# MorseKOB-Loop-w_PS_v6_eagle.net
KiCad netlist of a schematic drawn in EAGLE
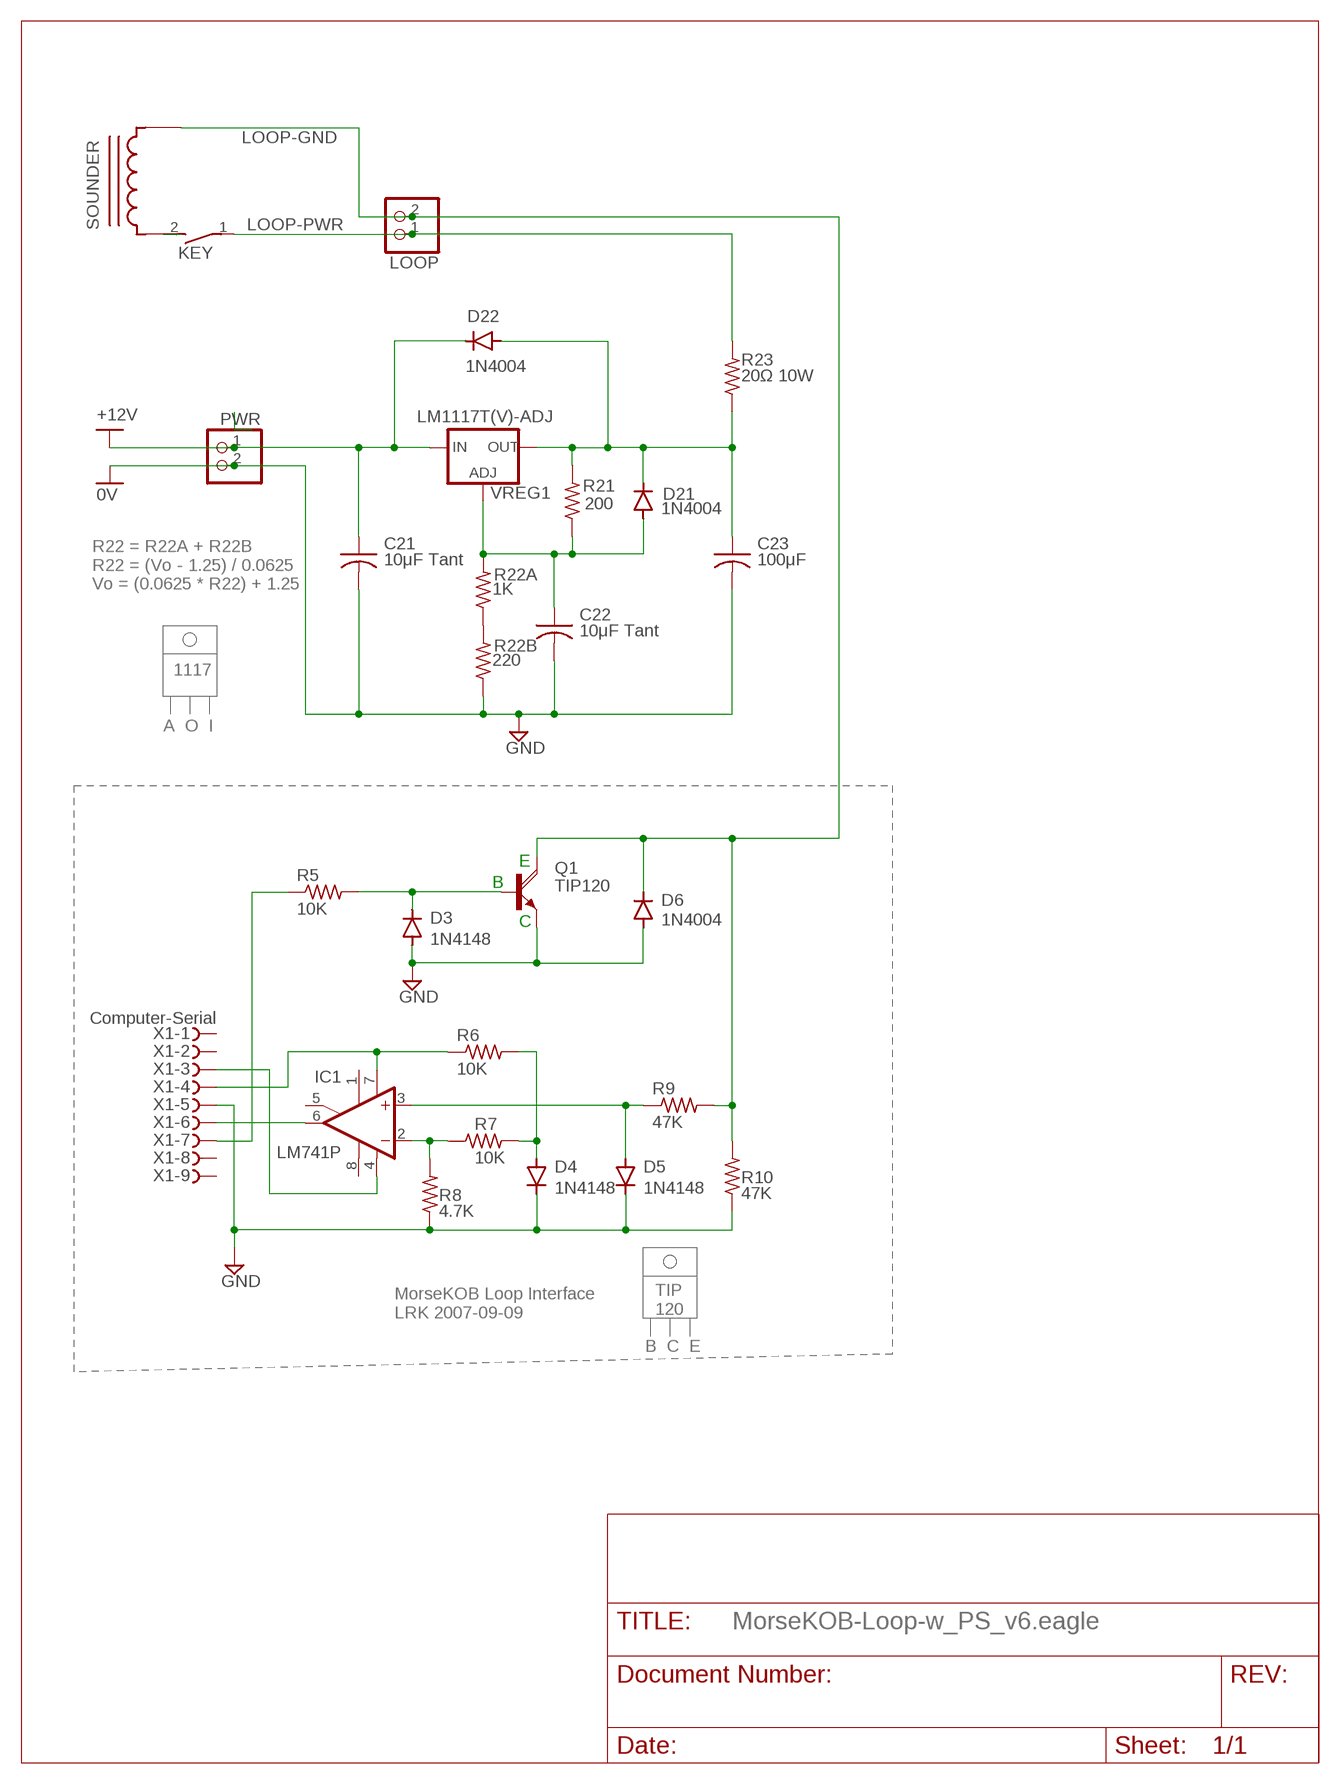
[diagram p0: schematic, sheet 1]

(export (version "E")
  (design (tool "Eeschema 10.0.6"))
  (components
    (comp (ref "C21")
      (value "10μF Tant")
      (footprint "eagle-import:C050-075X075")
      (libsource (lib "eagle-import") (part "C-US050-075X075"))
    )
    (comp (ref "C22")
      (value "10μF Tant")
      (footprint "eagle-import:C050-075X075")
      (libsource (lib "eagle-import") (part "C-US050-075X075"))
    )
    (comp (ref "C23")
      (value "100μF")
      (footprint "eagle-import:C025-050X050")
      (libsource (lib "eagle-import") (part "C-US025-050X050"))
    )
    (comp (ref "D3")
      (value "1N4148DO35-7")
      (footprint "eagle-import:DO35-7")
      (fields (field (name "TYPE") "1N4148"))
      (libsource (lib "eagle-import") (part "1N4148DO35-7"))
    )
    (comp (ref "D4")
      (value "1N4148DO35-7")
      (footprint "eagle-import:DO35-7")
      (fields (field (name "TYPE") "1N4148"))
      (libsource (lib "eagle-import") (part "1N4148DO35-7"))
    )
    (comp (ref "D5")
      (value "1N4148DO35-7")
      (footprint "eagle-import:DO35-7")
      (fields (field (name "TYPE") "1N4148"))
      (libsource (lib "eagle-import") (part "1N4148DO35-7"))
    )
    (comp (ref "D6")
      (value "1N4004")
      (footprint "eagle-import:DO41-10")
      (libsource (lib "eagle-import") (part "diode_210_1N4004"))
    )
    (comp (ref "D21")
      (value "1N4004")
      (footprint "eagle-import:DO-41")
      (fields
        (field (name "DIGIKEY_PART_NUMBER") "1N4004MSCT-ND")
        (field (name "MANUFACTURER") "Micro Commercial Co")
        (field (name "CREATED_BY") "PCBLayout.com")
      )
      (libsource (lib "eagle-import") (part "1N4004"))
    )
    (comp (ref "D22")
      (value "1N4004")
      (footprint "eagle-import:DO-41")
      (fields
        (field (name "DIGIKEY_PART_NUMBER") "1N4004MSCT-ND")
        (field (name "MANUFACTURER") "Micro Commercial Co")
        (field (name "CREATED_BY") "PCBLayout.com")
      )
      (libsource (lib "eagle-import") (part "1N4004"))
    )
    (comp (ref "IC1")
      (value "LM741P")
      (footprint "eagle-import:DIL08")
      (libsource (lib "eagle-import") (part "741PLM"))
    )
    (comp (ref "KEY")
      (value "DS01E")
      (footprint "eagle-import:DS-01")
      (libsource (lib "eagle-import") (part "DS01E"))
    )
    (comp (ref "LOOP")
      (value "PINHD-1X2")
      (footprint "eagle-import:1X02")
      (libsource (lib "eagle-import") (part "PINHD-1X2"))
    )
    (comp (ref "PWR")
      (value "PINHD-1X2")
      (footprint "eagle-import:1X02")
      (libsource (lib "eagle-import") (part "PINHD-1X2"))
    )
    (comp (ref "Q1")
      (value "TIP120")
      (footprint "eagle-import:TO220AH")
      (libsource (lib "eagle-import") (part "TIP120"))
    )
    (comp (ref "R5")
      (value "10K")
      (footprint "eagle-import:0207_10")
      (libsource (lib "eagle-import") (part "R-US_0207/10"))
    )
    (comp (ref "R6")
      (value "10K")
      (footprint "eagle-import:0207_10")
      (libsource (lib "eagle-import") (part "R-US_0207/10"))
    )
    (comp (ref "R7")
      (value "10K")
      (footprint "eagle-import:0207_10")
      (libsource (lib "eagle-import") (part "R-US_0207/10"))
    )
    (comp (ref "R8")
      (value "4.7K")
      (footprint "eagle-import:0207_10")
      (libsource (lib "eagle-import") (part "R-US_0207/10"))
    )
    (comp (ref "R9")
      (value "47K")
      (footprint "eagle-import:0207_10")
      (libsource (lib "eagle-import") (part "R-US_0207/10"))
    )
    (comp (ref "R10")
      (value "47K")
      (footprint "eagle-import:0207_10")
      (libsource (lib "eagle-import") (part "R-US_0207/10"))
    )
    (comp (ref "R21")
      (value "200")
      (footprint "eagle-import:0207_10")
      (libsource (lib "eagle-import") (part "R-US_0207/10"))
    )
    (comp (ref "R22A")
      (value "1K")
      (footprint "eagle-import:0207_10")
      (libsource (lib "eagle-import") (part "R-US_0207/10"))
    )
    (comp (ref "R22B")
      (value "220")
      (footprint "eagle-import:0207_10")
      (libsource (lib "eagle-import") (part "R-US_0207/10"))
    )
    (comp (ref "R23")
      (value "20Ω 10W")
      (footprint "eagle-import:0922_22")
      (libsource (lib "eagle-import") (part "R-US_0922/22"))
    )
    (comp (ref "SOUNDER")
      (value "T37_INDUCTOR")
      (footprint "eagle-import:T37_INDUCTOR")
      (libsource (lib "eagle-import") (part "T37_INDUCTOR"))
    )
    (comp (ref "VREG1")
      (value "LM1117T(V)-ADJ")
      (footprint "eagle-import:TO220V")
      (fields (field (name "MF") "Texas Instruments") (field (name "MPN") "LM1777T-ADJ"))
      (libsource (lib "eagle-import") (part "LM1117?-ADJT(V)"))
    )
    (comp (ref "X1")
      (value "Computer-Serial")
      (footprint "eagle-import:177-009-FEMALE")
      (libsource (lib "eagle-import") (part "F09?S.590"))
    )
  )
  (nets
    (net (code "1") (name "+12V") (class "Default")
      (node (ref "C21") (pin "1") (pinfunction "1_1") (pintype "passive"))
      (node (ref "D22") (pin "C") (pinfunction "C_C") (pintype "passive"))
      (node (ref "PWR") (pin "1") (pinfunction "1_1") (pintype "passive"))
      (node (ref "VREG1") (pin "3") (pinfunction "IN_3") (pintype "input"))
    )
    (net (code "2") (name "/LOOP-GND") (class "Default")
      (node (ref "D6") (pin "C") (pinfunction "C_C") (pintype "passive"))
      (node (ref "LOOP") (pin "2") (pinfunction "2_2") (pintype "passive"))
      (node (ref "Q1") (pin "C") (pinfunction "C_C") (pintype "passive"))
      (node (ref "R10") (pin "2") (pinfunction "2_2") (pintype "passive"))
      (node (ref "R9") (pin "2") (pinfunction "2_2") (pintype "passive"))
      (node (ref "SOUNDER") (pin "CA") (pinfunction "CA_CA") (pintype "bidirectional"))
    )
    (net (code "3") (name "/LOOP-PWR") (class "Default")
      (node (ref "KEY") (pin "1") (pinfunction "1_1") (pintype "passive"))
      (node (ref "LOOP") (pin "1") (pinfunction "1_1") (pintype "passive"))
      (node (ref "R23") (pin "2") (pinfunction "2_2") (pintype "passive"))
    )
    (net (code "4") (name "0V") (class "Default")
      (node (ref "C21") (pin "2") (pinfunction "2_2") (pintype "passive"))
      (node (ref "C22") (pin "2") (pinfunction "2_2") (pintype "passive"))
      (node (ref "C23") (pin "2") (pinfunction "2_2") (pintype "passive"))
      (node (ref "D3") (pin "A") (pinfunction "A_A") (pintype "passive"))
      (node (ref "D4") (pin "C") (pinfunction "C_C") (pintype "passive"))
      (node (ref "D5") (pin "C") (pinfunction "C_C") (pintype "passive"))
      (node (ref "D6") (pin "A") (pinfunction "A_A") (pintype "passive"))
      (node (ref "PWR") (pin "2") (pinfunction "2_2") (pintype "passive"))
      (node (ref "Q1") (pin "E") (pinfunction "E_E") (pintype "passive"))
      (node (ref "R10") (pin "1") (pinfunction "1_1") (pintype "passive"))
      (node (ref "R22B") (pin "1") (pinfunction "1_1") (pintype "passive"))
      (node (ref "R8") (pin "1") (pinfunction "1_1") (pintype "passive"))
      (node (ref "X1") (pin "5") (pinfunction "F_5") (pintype "passive"))
    )
    (net (code "5") (name "Net-(D3-PadC)") (class "Default")
      (node (ref "D3") (pin "C") (pinfunction "C_C") (pintype "passive"))
      (node (ref "Q1") (pin "B") (pinfunction "B_B") (pintype "passive"))
      (node (ref "R5") (pin "2") (pinfunction "2_2") (pintype "passive"))
    )
    (net (code "6") (name "Net-(D4-PadA)") (class "Default")
      (node (ref "D4") (pin "A") (pinfunction "A_A") (pintype "passive"))
      (node (ref "R6") (pin "2") (pinfunction "2_2") (pintype "passive"))
      (node (ref "R7") (pin "2") (pinfunction "2_2") (pintype "passive"))
    )
    (net (code "7") (name "Net-(IC1-+IN)") (class "Default")
      (node (ref "D5") (pin "A") (pinfunction "A_A") (pintype "passive"))
      (node (ref "IC1") (pin "3") (pinfunction "+IN_3") (pintype "input"))
      (node (ref "R9") (pin "1") (pinfunction "1_1") (pintype "passive"))
    )
    (net (code "8") (name "Net-(IC1--IN)") (class "Default")
      (node (ref "IC1") (pin "2") (pinfunction "-IN_2") (pintype "input"))
      (node (ref "R7") (pin "1") (pinfunction "1_1") (pintype "passive"))
      (node (ref "R8") (pin "2") (pinfunction "2_2") (pintype "passive"))
    )
    (net (code "9") (name "Net-(IC1-OUT)") (class "Default")
      (node (ref "IC1") (pin "6") (pinfunction "OUT_6") (pintype "output"))
      (node (ref "X1") (pin "6") (pinfunction "F_6") (pintype "passive"))
    )
    (net (code "10") (name "Net-(IC1-V+)") (class "Default")
      (node (ref "IC1") (pin "7") (pinfunction "V+_7") (pintype "power_in"))
      (node (ref "R6") (pin "1") (pinfunction "1_1") (pintype "passive"))
      (node (ref "X1") (pin "4") (pinfunction "F_4") (pintype "passive"))
    )
    (net (code "11") (name "Net-(IC1-V-)") (class "Default")
      (node (ref "IC1") (pin "4") (pinfunction "V-_4") (pintype "power_in"))
      (node (ref "X1") (pin "3") (pinfunction "F_3") (pintype "passive"))
    )
    (net (code "12") (name "Net-(KEY-Pad2)") (class "Default")
      (node (ref "KEY") (pin "2") (pinfunction "2_2") (pintype "passive"))
      (node (ref "SOUNDER") (pin "CB") (pinfunction "CB_CB") (pintype "bidirectional"))
    )
    (net (code "13") (name "Net-(R22A-Pad1)") (class "Default")
      (node (ref "R22A") (pin "1") (pinfunction "1_1") (pintype "passive"))
      (node (ref "R22B") (pin "2") (pinfunction "2_2") (pintype "passive"))
    )
    (net (code "14") (name "Net-(VREG1-ADJ)") (class "Default")
      (node (ref "C22") (pin "1") (pinfunction "1_1") (pintype "passive"))
      (node (ref "D21") (pin "A") (pinfunction "A_A") (pintype "passive"))
      (node (ref "R21") (pin "1") (pinfunction "1_1") (pintype "passive"))
      (node (ref "R22A") (pin "2") (pinfunction "2_2") (pintype "passive"))
      (node (ref "VREG1") (pin "1") (pinfunction "ADJ_1") (pintype "input"))
    )
    (net (code "15") (name "Net-(VREG1-OUT)") (class "Default")
      (node (ref "C23") (pin "1") (pinfunction "1_1") (pintype "passive"))
      (node (ref "D21") (pin "C") (pinfunction "C_C") (pintype "passive"))
      (node (ref "D22") (pin "A") (pinfunction "A_A") (pintype "passive"))
      (node (ref "R21") (pin "2") (pinfunction "2_2") (pintype "passive"))
      (node (ref "R23") (pin "1") (pinfunction "1_1") (pintype "passive"))
      (node (ref "VREG1") (pin "2") (pinfunction "OUT_2") (pintype "passive"))
    )
    (net (code "16") (name "Net-(X1G-F)") (class "Default")
      (node (ref "R5") (pin "1") (pinfunction "1_1") (pintype "passive"))
      (node (ref "X1") (pin "7") (pinfunction "F_7") (pintype "passive"))
    )
    (net (code "17") (name "unconnected-(IC1-ON1-Pad1)") (class "Default")
      (node (ref "IC1") (pin "1") (pinfunction "ON1_1") (pintype "passive"))
    )
    (net (code "18") (name "unconnected-(IC1-ON2-Pad5)") (class "Default")
      (node (ref "IC1") (pin "5") (pinfunction "ON2_5") (pintype "passive"))
    )
    (net (code "19") (name "unconnected-(IC1-OPT-Pad8)") (class "Default")
      (node (ref "IC1") (pin "8") (pinfunction "OPT_8") (pintype "passive"))
    )
    (net (code "20") (name "unconnected-(X1A-F-Pad1)") (class "Default")
      (node (ref "X1") (pin "1") (pinfunction "F_1") (pintype "passive"))
    )
    (net (code "21") (name "unconnected-(X1B-F-Pad2)") (class "Default")
      (node (ref "X1") (pin "2") (pinfunction "F_2") (pintype "passive"))
    )
    (net (code "22") (name "unconnected-(X1H-F-Pad8)") (class "Default")
      (node (ref "X1") (pin "8") (pinfunction "F_8") (pintype "passive"))
    )
    (net (code "23") (name "unconnected-(X1I-F-Pad9)") (class "Default")
      (node (ref "X1") (pin "9") (pinfunction "F_9") (pintype "passive"))
    )
  )
)
